# MysensorsGW_huzzah.net
KiCad netlist of a schematic drawn in EAGLE
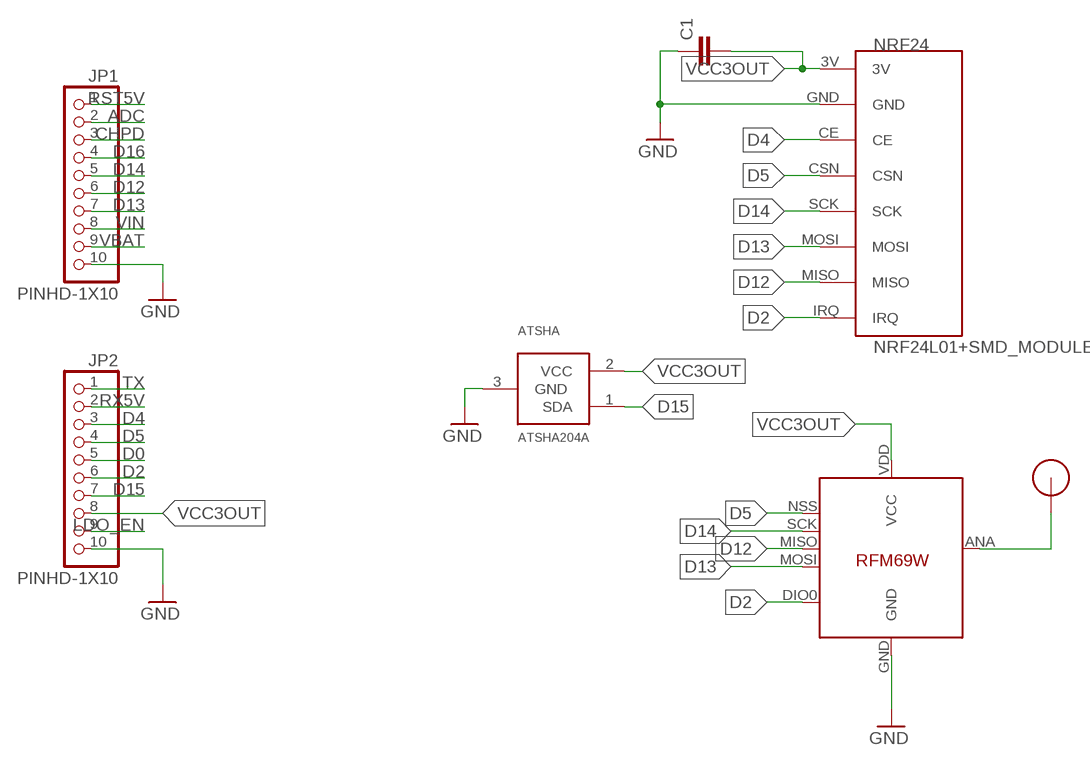
[diagram p0: schematic, sheet 1]

(export (version "E")
  (design (tool "Eeschema 10.0.6"))
  (components
    (comp (ref "ATSHA")
      (value "ATSHA204A")
      (footprint "eagle-import:SOT23")
      (libsource (lib "eagle-import") (part "ATSHA204A"))
    )
    (comp (ref "C1")
      (value "CAP1206")
      (footprint "eagle-import:1206")
      (libsource (lib "eagle-import") (part "CAP1206"))
    )
    (comp (ref "JP1")
      (value "PINHD-1X10")
      (footprint "eagle-import:1X10-BIG")
      (libsource (lib "eagle-import") (part "PINHD-1X10"))
    )
    (comp (ref "JP2")
      (value "PINHD-1X10")
      (footprint "eagle-import:1X10-BIG")
      (libsource (lib "eagle-import") (part "PINHD-1X10"))
    )
    (comp (ref "NRF24")
      (value "NRF24L01+SMD_MODULE")
      (footprint "eagle-import:NRF24L01+SMD_MODULE")
      (libsource (lib "eagle-import") (part "NRF24L01+SMD_MODULE"))
    )
    (comp (ref "RFM69")
      (value "RFM69")
      (footprint "eagle-import:RFM69W-MINPADS")
      (libsource (lib "eagle-import") (part "RFM69"))
    )
    (comp (ref "U$2")
      (value "RFM12B_ANTENNA")
      (footprint "eagle-import:RFM12B-ANTENNA")
      (libsource (lib "eagle-import") (part "RFM12B_ANTENNA"))
    )
  )
  (nets
    (net (code "1") (name "/ADC") (class "Default")
      (node (ref "JP1") (pin "2") (pinfunction "2_2") (pintype "passive"))
    )
    (net (code "2") (name "/CHPD") (class "Default")
      (node (ref "JP1") (pin "3") (pinfunction "3_3") (pintype "passive"))
    )
    (net (code "3") (name "/D0") (class "Default")
      (node (ref "JP2") (pin "5") (pinfunction "5_5") (pintype "passive"))
    )
    (net (code "4") (name "/D16") (class "Default")
      (node (ref "JP1") (pin "4") (pinfunction "4_4") (pintype "passive"))
    )
    (net (code "5") (name "/LDO_EN") (class "Default")
      (node (ref "JP2") (pin "9") (pinfunction "9_9") (pintype "passive"))
    )
    (net (code "6") (name "/RST5V") (class "Default")
      (node (ref "JP1") (pin "1") (pinfunction "1_1") (pintype "passive"))
    )
    (net (code "7") (name "/RX5V") (class "Default")
      (node (ref "JP2") (pin "2") (pinfunction "2_2") (pintype "passive"))
    )
    (net (code "8") (name "/TX") (class "Default")
      (node (ref "JP2") (pin "1") (pinfunction "1_1") (pintype "passive"))
    )
    (net (code "9") (name "/VBAT") (class "Default")
      (node (ref "JP1") (pin "9") (pinfunction "9_9") (pintype "passive"))
    )
    (net (code "10") (name "/VIN") (class "Default")
      (node (ref "JP1") (pin "8") (pinfunction "8_8") (pintype "passive"))
    )
    (net (code "11") (name "D2") (class "Default")
      (node (ref "JP2") (pin "6") (pinfunction "6_6") (pintype "passive"))
      (node (ref "NRF24") (pin "IRQ") (pinfunction "IRQ_IRQ") (pintype "bidirectional"))
      (node (ref "RFM69") (pin "DIO0") (pinfunction "DIO0_DIO0") (pintype "open_collector"))
    )
    (net (code "12") (name "D4") (class "Default")
      (node (ref "JP2") (pin "3") (pinfunction "3_3") (pintype "passive"))
      (node (ref "NRF24") (pin "CE") (pinfunction "CE_CE") (pintype "bidirectional"))
    )
    (net (code "13") (name "D5") (class "Default")
      (node (ref "JP2") (pin "4") (pinfunction "4_4") (pintype "passive"))
      (node (ref "NRF24") (pin "CSN") (pinfunction "CSN_CSN") (pintype "bidirectional"))
      (node (ref "RFM69") (pin "NSS") (pinfunction "SEL_NSS") (pintype "input"))
    )
    (net (code "14") (name "D12") (class "Default")
      (node (ref "JP1") (pin "6") (pinfunction "6_6") (pintype "passive"))
      (node (ref "NRF24") (pin "MISO") (pinfunction "MISO_MISO") (pintype "bidirectional"))
      (node (ref "RFM69") (pin "MISO") (pinfunction "MISO_MISO") (pintype "input"))
    )
    (net (code "15") (name "D13") (class "Default")
      (node (ref "JP1") (pin "7") (pinfunction "7_7") (pintype "passive"))
      (node (ref "NRF24") (pin "MOSI") (pinfunction "MOSI_MOSI") (pintype "bidirectional"))
      (node (ref "RFM69") (pin "MOSI") (pinfunction "MOSI_MOSI") (pintype "output"))
    )
    (net (code "16") (name "D14") (class "Default")
      (node (ref "JP1") (pin "5") (pinfunction "5_5") (pintype "passive"))
      (node (ref "NRF24") (pin "SCK") (pinfunction "SCK_SCK") (pintype "bidirectional"))
      (node (ref "RFM69") (pin "SCK") (pinfunction "SCK_SCK") (pintype "input"))
    )
    (net (code "17") (name "D15") (class "Default")
      (node (ref "ATSHA") (pin "1") (pinfunction "SDA_1") (pintype "bidirectional"))
      (node (ref "JP2") (pin "7") (pinfunction "7_7") (pintype "passive"))
    )
    (net (code "18") (name "GND") (class "Default")
      (node (ref "ATSHA") (pin "3") (pinfunction "GND_3") (pintype "bidirectional"))
      (node (ref "C1") (pin "1") (pinfunction "1_1") (pintype "passive"))
      (node (ref "JP1") (pin "10") (pinfunction "10_10") (pintype "passive"))
      (node (ref "JP2") (pin "10") (pinfunction "10_10") (pintype "passive"))
      (node (ref "NRF24") (pin "GND") (pinfunction "GND_GND") (pintype "bidirectional"))
      (node (ref "RFM69") (pin "GND") (pinfunction "GND_GND") (pintype "power_in"))
    )
    (net (code "19") (name "Net-(RFM69-ANT)") (class "Default")
      (node (ref "RFM69") (pin "ANA") (pinfunction "ANT_ANA") (pintype "passive"))
      (node (ref "U$2") (pin "P$1") (pinfunction "1_P$1") (pintype "bidirectional"))
    )
    (net (code "20") (name "VCC3OUT") (class "Default")
      (node (ref "ATSHA") (pin "2") (pinfunction "VCC_2") (pintype "bidirectional"))
      (node (ref "C1") (pin "2") (pinfunction "2_2") (pintype "passive"))
      (node (ref "JP2") (pin "8") (pinfunction "8_8") (pintype "passive"))
      (node (ref "NRF24") (pin "3V") (pinfunction "3V_3V") (pintype "bidirectional"))
      (node (ref "RFM69") (pin "VDD") (pinfunction "VCC_VDD") (pintype "power_in"))
    )
  )
)
